# ProProject_FYP_2025-03-13.net
KiCad netlist of a schematic drawn in EasyEDA Pro
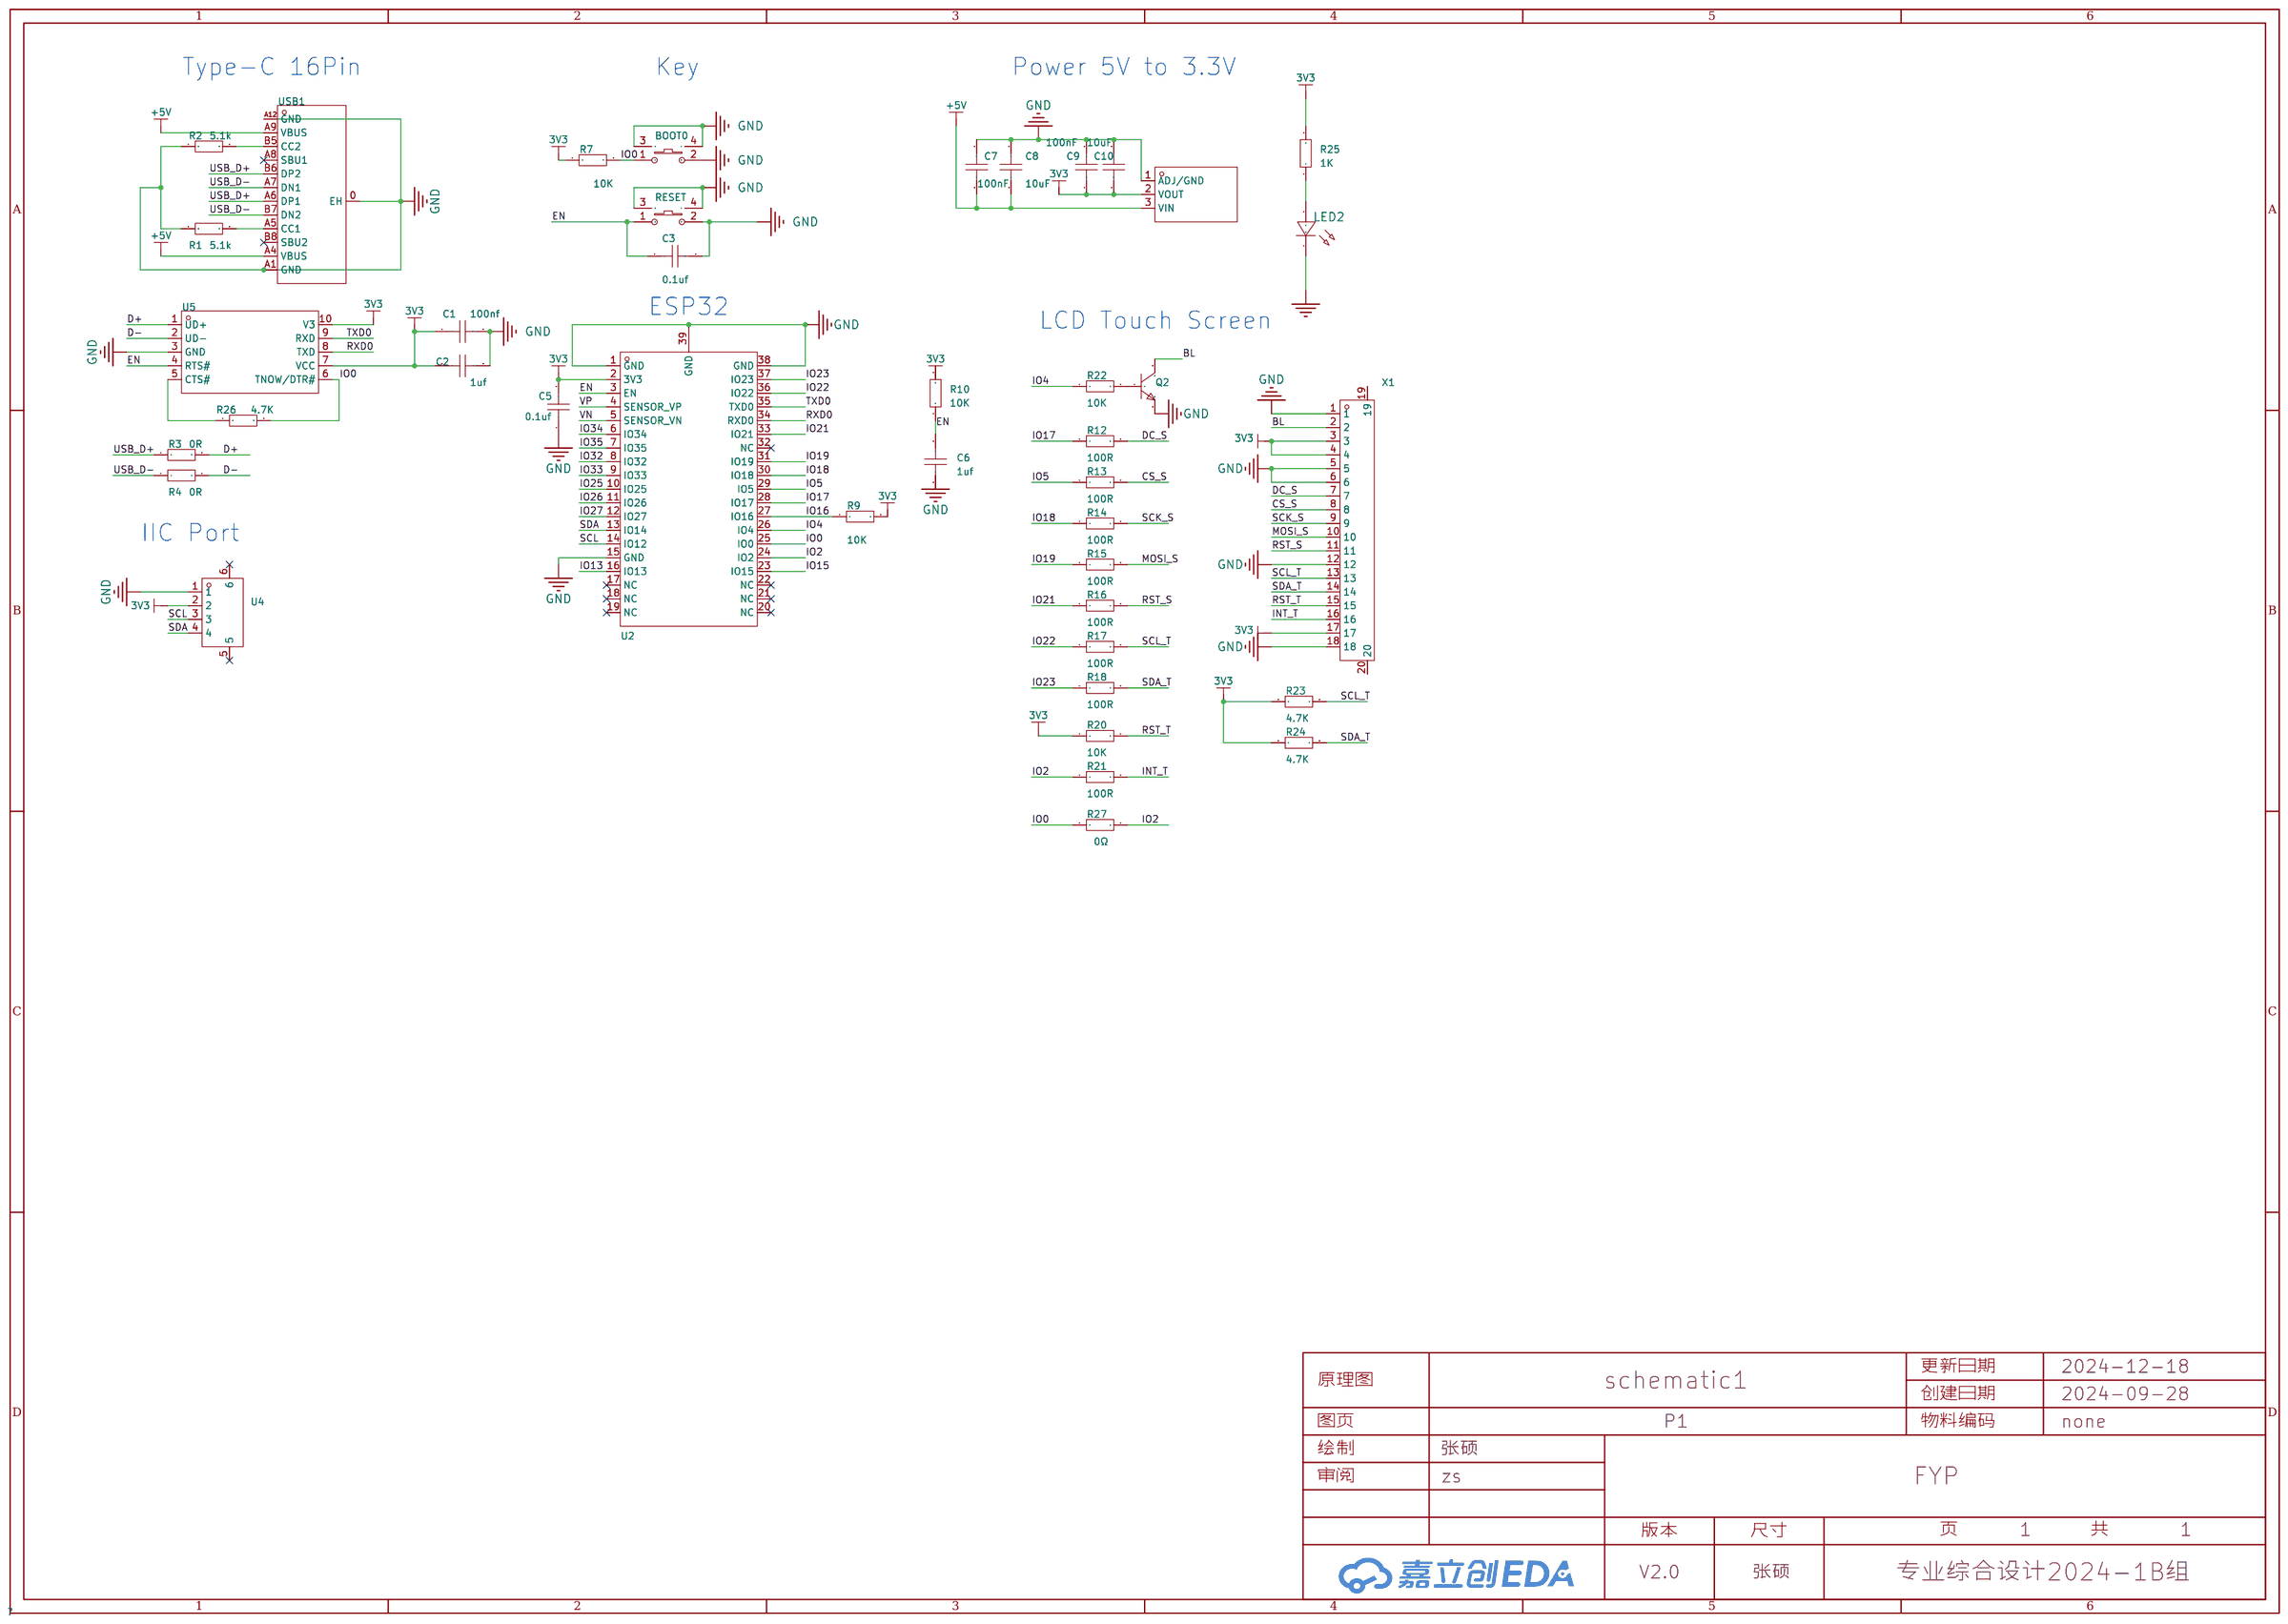
[diagram p0: schematic sheet]

(export (version "E")
  (design (tool "Eeschema 10.0.6"))
  (components
    (comp (ref "BOOT0")
      (value "TS24CA 250gf 013")
      (footprint "easyedapro:SW-SMD_L4.7-W3.5-P3.35-EH")
      (fields (field (name "Manufacturer") "SHOU HAN(首韩)"))
      (libsource (lib "easyedapro") (part "TS24CA 250GF 013"))
    )
    (comp (ref "C1")
      (value "100nf")
      (footprint "easyedapro:C0603")
      (libsource (lib "easyedapro") (part "CapAcitance"))
    )
    (comp (ref "C2")
      (value "1uf")
      (footprint "easyedapro:C0603")
      (libsource (lib "easyedapro") (part "CapAcitance"))
    )
    (comp (ref "C3")
      (value "0.1uf")
      (footprint "easyedapro:C0603")
      (libsource (lib "easyedapro") (part "CapAcitance"))
    )
    (comp (ref "C5")
      (value "0.1uf")
      (footprint "easyedapro:C0603")
      (libsource (lib "easyedapro") (part "CapAcitance"))
    )
    (comp (ref "C6")
      (value "1uf")
      (footprint "easyedapro:C0603")
      (libsource (lib "easyedapro") (part "CapAcitance"))
    )
    (comp (ref "C7")
      (value "100nF")
      (footprint "easyedapro:C0603")
      (libsource (lib "easyedapro") (part "CapAcitance"))
    )
    (comp (ref "C8")
      (value "10uF")
      (footprint "easyedapro:C0603")
      (libsource (lib "easyedapro") (part "CapAcitance"))
    )
    (comp (ref "C9")
      (value "100nF")
      (footprint "easyedapro:C0603")
      (libsource (lib "easyedapro") (part "CapAcitance"))
    )
    (comp (ref "C10")
      (value "10uF")
      (footprint "easyedapro:C0603")
      (libsource (lib "easyedapro") (part "CapAcitance"))
    )
    (comp (ref "LED2")
      (value "~")
      (footprint "easyedapro:LED_0603")
      (libsource (lib "easyedapro") (part "LED_R"))
    )
    (comp (ref "Q2")
      (value "~")
      (footprint "easyedapro:S8050_SOT-23")
      (libsource (lib "easyedapro") (part "NPN"))
    )
    (comp (ref "Q4")
      (value "AMS1117-3.3V")
      (footprint "easyedapro:SOT-89-3_L4.5-W2.5-P1.50-LS4.2-BR")
      (description "输出类型:固定;最大输入电压:18V;输出电压:3.3V;最大输出电流:1A;输出极性:正极;")
      (fields (field (name "Manufacturer") "MSKSEMI(美森科)"))
      (libsource (lib "easyedapro") (part "AMS1117-3.3V_C5120796"))
    )
    (comp (ref "R1") (value "5.1k") (footprint "easyedapro:R0402") (libsource (lib "easyedapro") (part "电阻")))
    (comp (ref "R2") (value "5.1k") (footprint "easyedapro:R0402") (libsource (lib "easyedapro") (part "电阻")))
    (comp (ref "R3") (value "0R") (footprint "easyedapro:R0402") (libsource (lib "easyedapro") (part "电阻")))
    (comp (ref "R4") (value "0R") (footprint "easyedapro:R0402") (libsource (lib "easyedapro") (part "电阻")))
    (comp (ref "R7") (value "10K") (footprint "easyedapro:R0402") (libsource (lib "easyedapro") (part "电阻")))
    (comp (ref "R9") (value "10K") (footprint "easyedapro:R0402") (libsource (lib "easyedapro") (part "电阻")))
    (comp (ref "R10") (value "10K") (footprint "easyedapro:R0402") (libsource (lib "easyedapro") (part "电阻")))
    (comp (ref "R12")
      (value "100R")
      (footprint "easyedapro:R0402")
      (libsource (lib "easyedapro") (part "电阻"))
    )
    (comp (ref "R13")
      (value "100R")
      (footprint "easyedapro:R0402")
      (libsource (lib "easyedapro") (part "电阻"))
    )
    (comp (ref "R14")
      (value "100R")
      (footprint "easyedapro:R0402")
      (libsource (lib "easyedapro") (part "电阻"))
    )
    (comp (ref "R15")
      (value "100R")
      (footprint "easyedapro:R0402")
      (libsource (lib "easyedapro") (part "电阻"))
    )
    (comp (ref "R16")
      (value "100R")
      (footprint "easyedapro:R0402")
      (libsource (lib "easyedapro") (part "电阻"))
    )
    (comp (ref "R17")
      (value "100R")
      (footprint "easyedapro:R0402")
      (libsource (lib "easyedapro") (part "电阻"))
    )
    (comp (ref "R18")
      (value "100R")
      (footprint "easyedapro:R0402")
      (libsource (lib "easyedapro") (part "电阻"))
    )
    (comp (ref "R20") (value "10K") (footprint "easyedapro:R0402") (libsource (lib "easyedapro") (part "电阻")))
    (comp (ref "R21")
      (value "100R")
      (footprint "easyedapro:R0402")
      (libsource (lib "easyedapro") (part "电阻"))
    )
    (comp (ref "R22") (value "10K") (footprint "easyedapro:R0402") (libsource (lib "easyedapro") (part "电阻")))
    (comp (ref "R23")
      (value "4.7K")
      (footprint "easyedapro:R0402")
      (libsource (lib "easyedapro") (part "电阻"))
    )
    (comp (ref "R24")
      (value "4.7K")
      (footprint "easyedapro:R0402")
      (libsource (lib "easyedapro") (part "电阻"))
    )
    (comp (ref "R25") (value "1K") (footprint "easyedapro:R0402") (libsource (lib "easyedapro") (part "电阻")))
    (comp (ref "R26")
      (value "4.7K")
      (footprint "easyedapro:R0402")
      (libsource (lib "easyedapro") (part "电阻"))
    )
    (comp (ref "R27") (value "0Ω") (footprint "easyedapro:R0402") (libsource (lib "easyedapro") (part "电阻")))
    (comp (ref "RESET")
      (value "TS24CA 250gf 013")
      (footprint "easyedapro:SW-SMD_L4.7-W3.5-P3.35-EH")
      (fields (field (name "Manufacturer") "SHOU HAN(首韩)"))
      (libsource (lib "easyedapro") (part "TS24CA 250GF 013"))
    )
    (comp (ref "U2")
      (value "ESP32-WROOM-32E-N4")
      (footprint "easyedapro:WIFI-SMD_ESP32-WROOM-32E")
      (description "ESP32-WROOM-32E 集成 ESP32-D0WD-V3 芯片，具有高的稳定性和安全性能。")
      (fields (field (name "Manufacturer") "ESPRESSIF(乐鑫)"))
      (libsource (lib "easyedapro") (part "ESP32-WROOM-32E(4MB)"))
    )
    (comp (ref "U4")
      (value "WAFER-GH1.25-4PWB")
      (footprint "easyedapro:CONN-SMD_4P-P1.25_XUNPU_WAFER-GH1.25-4PWB")
      (description "插针结构:1x4P;间距:1.25mm;安装方式:卧贴;参考系列:GH;总PIN数:4P;排数:1;每排PIN数:4;额定电流:1A;工作温度范围:-25°C~+85°C;")
      (fields (field (name "Manufacturer") "XUNPU(讯普)"))
      (libsource (lib "easyedapro") (part "WAFER-GH1.25-4PWB"))
    )
    (comp (ref "U5")
      (value "CH340X")
      (footprint "easyedapro:MSOP-10_L3.0-W3.0-P0.50-LS5.0-BL")
      (fields (field (name "Manufacturer") "WCH(南京沁恒)"))
      (libsource (lib "easyedapro") (part "CH340X"))
    )
    (comp (ref "USB1")
      (value "TYPE-C 16P QTWT")
      (footprint "easyedapro:USB-TYPE-C-SMD_TYPE-C-16P-QTWT")
      (fields (field (name "Manufacturer") "SHOU HAN(首韩)"))
      (libsource (lib "easyedapro") (part "TYPE-C 16P QTWT"))
    )
    (comp (ref "X1")
      (value "AFC07-S18FCA-00")
      (footprint "easyedapro:FPC-SMD_AFC07-S18FCA-00")
      (description "锁定特性:抽屉式;触点类型:下接;触点数量:18P;间距:0.5mm;安装类型:卧贴;工作温度范围:-;")
      (fields (field (name "Manufacturer") "JS(钜硕电子)"))
      (libsource (lib "easyedapro") (part "AFC07-S18FCA-00"))
    )
  )
  (nets
    (net (code "1") (name "+5V") (class "Default")
      (node (ref "C7") (pin "1") (pinfunction "1_1") (pintype "input"))
      (node (ref "C8") (pin "1") (pinfunction "1_1") (pintype "input"))
      (node (ref "Q4") (pin "3") (pinfunction "VIN_3") (pintype "unspecified"))
      (node (ref "USB1") (pin "A4") (pinfunction "VBUS_A4") (pintype "unspecified"))
      (node (ref "USB1") (pin "A9") (pinfunction "VBUS_A9") (pintype "unspecified"))
    )
    (net (code "2") (name "/BL") (class "Default")
      (node (ref "Q2") (pin "3") (pinfunction "3_3") (pintype "unspecified"))
      (node (ref "X1") (pin "2") (pinfunction "2_2") (pintype "unspecified"))
    )
    (net (code "3") (name "/CS_S") (class "Default")
      (node (ref "R13") (pin "2") (pinfunction "2_2") (pintype "input"))
      (node (ref "X1") (pin "8") (pinfunction "8_8") (pintype "unspecified"))
    )
    (net (code "4") (name "/D+") (class "Default")
      (node (ref "R3") (pin "2") (pinfunction "2_2") (pintype "input"))
      (node (ref "U5") (pin "1") (pinfunction "UD+_1") (pintype "unspecified"))
    )
    (net (code "5") (name "/D-") (class "Default")
      (node (ref "R4") (pin "2") (pinfunction "2_2") (pintype "input"))
      (node (ref "U5") (pin "2") (pinfunction "UD-_2") (pintype "unspecified"))
    )
    (net (code "6") (name "/DC_S") (class "Default")
      (node (ref "R12") (pin "2") (pinfunction "2_2") (pintype "input"))
      (node (ref "X1") (pin "7") (pinfunction "7_7") (pintype "unspecified"))
    )
    (net (code "7") (name "/EN") (class "Default")
      (node (ref "C3") (pin "1") (pinfunction "1_1") (pintype "input"))
      (node (ref "C6") (pin "1") (pinfunction "1_1") (pintype "input"))
      (node (ref "R10") (pin "1") (pinfunction "1_1") (pintype "input"))
      (node (ref "RESET") (pin "1") (pinfunction "1_1") (pintype "unspecified"))
      (node (ref "U2") (pin "3") (pinfunction "EN_3") (pintype "unspecified"))
      (node (ref "U5") (pin "4") (pinfunction "RTS#_4") (pintype "unspecified"))
    )
    (net (code "8") (name "/INT_T") (class "Default")
      (node (ref "R21") (pin "2") (pinfunction "2_2") (pintype "input"))
      (node (ref "X1") (pin "16") (pinfunction "16_16") (pintype "unspecified"))
    )
    (net (code "9") (name "/IO0") (class "Default")
      (node (ref "BOOT0") (pin "1") (pinfunction "1_1") (pintype "unspecified"))
      (node (ref "R26") (pin "2") (pinfunction "2_2") (pintype "input"))
      (node (ref "R27") (pin "1") (pinfunction "1_1") (pintype "input"))
      (node (ref "R7") (pin "2") (pinfunction "2_2") (pintype "input"))
      (node (ref "U2") (pin "25") (pinfunction "IO0_25") (pintype "unspecified"))
      (node (ref "U5") (pin "6") (pinfunction "TNOW/DTR#_6") (pintype "unspecified"))
    )
    (net (code "10") (name "/IO2") (class "Default")
      (node (ref "R21") (pin "1") (pinfunction "1_1") (pintype "input"))
      (node (ref "R27") (pin "2") (pinfunction "2_2") (pintype "input"))
      (node (ref "U2") (pin "24") (pinfunction "IO2_24") (pintype "unspecified"))
    )
    (net (code "11") (name "/IO4") (class "Default")
      (node (ref "R22") (pin "1") (pinfunction "1_1") (pintype "input"))
      (node (ref "U2") (pin "26") (pinfunction "IO4_26") (pintype "unspecified"))
    )
    (net (code "12") (name "/IO5") (class "Default")
      (node (ref "R13") (pin "1") (pinfunction "1_1") (pintype "input"))
      (node (ref "U2") (pin "29") (pinfunction "IO5_29") (pintype "unspecified"))
    )
    (net (code "13") (name "/IO13") (class "Default")
      (node (ref "U2") (pin "16") (pinfunction "IO13_16") (pintype "unspecified"))
    )
    (net (code "14") (name "/IO15") (class "Default")
      (node (ref "U2") (pin "23") (pinfunction "IO15_23") (pintype "unspecified"))
    )
    (net (code "15") (name "/IO16") (class "Default")
      (node (ref "R9") (pin "1") (pinfunction "1_1") (pintype "input"))
      (node (ref "U2") (pin "27") (pinfunction "IO16_27") (pintype "unspecified"))
    )
    (net (code "16") (name "/IO17") (class "Default")
      (node (ref "R12") (pin "1") (pinfunction "1_1") (pintype "input"))
      (node (ref "U2") (pin "28") (pinfunction "IO17_28") (pintype "unspecified"))
    )
    (net (code "17") (name "/IO18") (class "Default")
      (node (ref "R14") (pin "1") (pinfunction "1_1") (pintype "input"))
      (node (ref "U2") (pin "30") (pinfunction "IO18_30") (pintype "unspecified"))
    )
    (net (code "18") (name "/IO19") (class "Default")
      (node (ref "R15") (pin "1") (pinfunction "1_1") (pintype "input"))
      (node (ref "U2") (pin "31") (pinfunction "IO19_31") (pintype "unspecified"))
    )
    (net (code "19") (name "/IO21") (class "Default")
      (node (ref "R16") (pin "1") (pinfunction "1_1") (pintype "input"))
      (node (ref "U2") (pin "33") (pinfunction "IO21_33") (pintype "unspecified"))
    )
    (net (code "20") (name "/IO22") (class "Default")
      (node (ref "R17") (pin "1") (pinfunction "1_1") (pintype "input"))
      (node (ref "U2") (pin "36") (pinfunction "IO22_36") (pintype "unspecified"))
    )
    (net (code "21") (name "/IO23") (class "Default")
      (node (ref "R18") (pin "1") (pinfunction "1_1") (pintype "input"))
      (node (ref "U2") (pin "37") (pinfunction "IO23_37") (pintype "unspecified"))
    )
    (net (code "22") (name "/IO25") (class "Default")
      (node (ref "U2") (pin "10") (pinfunction "IO25_10") (pintype "unspecified"))
    )
    (net (code "23") (name "/IO26") (class "Default")
      (node (ref "U2") (pin "11") (pinfunction "IO26_11") (pintype "unspecified"))
    )
    (net (code "24") (name "/IO27") (class "Default")
      (node (ref "U2") (pin "12") (pinfunction "IO27_12") (pintype "unspecified"))
    )
    (net (code "25") (name "/IO32") (class "Default")
      (node (ref "U2") (pin "8") (pinfunction "IO32_8") (pintype "unspecified"))
    )
    (net (code "26") (name "/IO33") (class "Default")
      (node (ref "U2") (pin "9") (pinfunction "IO33_9") (pintype "unspecified"))
    )
    (net (code "27") (name "/IO34") (class "Default")
      (node (ref "U2") (pin "6") (pinfunction "IO34_6") (pintype "unspecified"))
    )
    (net (code "28") (name "/IO35") (class "Default")
      (node (ref "U2") (pin "7") (pinfunction "IO35_7") (pintype "unspecified"))
    )
    (net (code "29") (name "/MOSI_S") (class "Default")
      (node (ref "R15") (pin "2") (pinfunction "2_2") (pintype "input"))
      (node (ref "X1") (pin "10") (pinfunction "10_10") (pintype "unspecified"))
    )
    (net (code "30") (name "/RST_S") (class "Default")
      (node (ref "R16") (pin "2") (pinfunction "2_2") (pintype "input"))
      (node (ref "X1") (pin "11") (pinfunction "11_11") (pintype "unspecified"))
    )
    (net (code "31") (name "/RST_T") (class "Default")
      (node (ref "R20") (pin "2") (pinfunction "2_2") (pintype "input"))
      (node (ref "X1") (pin "15") (pinfunction "15_15") (pintype "unspecified"))
    )
    (net (code "32") (name "/RXD0") (class "Default")
      (node (ref "U2") (pin "34") (pinfunction "RXD0_34") (pintype "unspecified"))
      (node (ref "U5") (pin "8") (pinfunction "TXD_8") (pintype "unspecified"))
    )
    (net (code "33") (name "/SCK_S") (class "Default")
      (node (ref "R14") (pin "2") (pinfunction "2_2") (pintype "input"))
      (node (ref "X1") (pin "9") (pinfunction "9_9") (pintype "unspecified"))
    )
    (net (code "34") (name "/SCL") (class "Default")
      (node (ref "U2") (pin "14") (pinfunction "IO12_14") (pintype "unspecified"))
      (node (ref "U4") (pin "3") (pinfunction "3_3") (pintype "unspecified"))
    )
    (net (code "35") (name "/SCL_T") (class "Default")
      (node (ref "R17") (pin "2") (pinfunction "2_2") (pintype "input"))
      (node (ref "R23") (pin "2") (pinfunction "2_2") (pintype "input"))
      (node (ref "X1") (pin "13") (pinfunction "13_13") (pintype "unspecified"))
    )
    (net (code "36") (name "/SDA") (class "Default")
      (node (ref "U2") (pin "13") (pinfunction "IO14_13") (pintype "unspecified"))
      (node (ref "U4") (pin "4") (pinfunction "4_4") (pintype "unspecified"))
    )
    (net (code "37") (name "/SDA_T") (class "Default")
      (node (ref "R18") (pin "2") (pinfunction "2_2") (pintype "input"))
      (node (ref "R24") (pin "2") (pinfunction "2_2") (pintype "input"))
      (node (ref "X1") (pin "14") (pinfunction "14_14") (pintype "unspecified"))
    )
    (net (code "38") (name "/TXD0") (class "Default")
      (node (ref "U2") (pin "35") (pinfunction "TXD0_35") (pintype "unspecified"))
      (node (ref "U5") (pin "9") (pinfunction "RXD_9") (pintype "unspecified"))
    )
    (net (code "39") (name "/USB_D+") (class "Default")
      (node (ref "R3") (pin "1") (pinfunction "1_1") (pintype "input"))
      (node (ref "USB1") (pin "A6") (pinfunction "DP1_A6") (pintype "unspecified"))
      (node (ref "USB1") (pin "B6") (pinfunction "DP2_B6") (pintype "unspecified"))
    )
    (net (code "40") (name "/USB_D-") (class "Default")
      (node (ref "R4") (pin "1") (pinfunction "1_1") (pintype "input"))
      (node (ref "USB1") (pin "A7") (pinfunction "DN1_A7") (pintype "unspecified"))
      (node (ref "USB1") (pin "B7") (pinfunction "DN2_B7") (pintype "unspecified"))
    )
    (net (code "41") (name "/VN") (class "Default")
      (node (ref "U2") (pin "5") (pinfunction "SENSOR_VN_5") (pintype "unspecified"))
    )
    (net (code "42") (name "/VP") (class "Default")
      (node (ref "U2") (pin "4") (pinfunction "SENSOR_VP_4") (pintype "unspecified"))
    )
    (net (code "43") (name "3V3") (class "Default")
      (node (ref "C1") (pin "1") (pinfunction "1_1") (pintype "input"))
      (node (ref "C10") (pin "1") (pinfunction "1_1") (pintype "input"))
      (node (ref "C2") (pin "1") (pinfunction "1_1") (pintype "input"))
      (node (ref "C5") (pin "2") (pinfunction "2_2") (pintype "input"))
      (node (ref "C9") (pin "1") (pinfunction "1_1") (pintype "input"))
      (node (ref "Q4") (pin "2") (pinfunction "VOUT_2") (pintype "unspecified"))
      (node (ref "R10") (pin "2") (pinfunction "2_2") (pintype "input"))
      (node (ref "R20") (pin "1") (pinfunction "1_1") (pintype "input"))
      (node (ref "R23") (pin "1") (pinfunction "1_1") (pintype "input"))
      (node (ref "R24") (pin "1") (pinfunction "1_1") (pintype "input"))
      (node (ref "R25") (pin "2") (pinfunction "2_2") (pintype "input"))
      (node (ref "R7") (pin "1") (pinfunction "1_1") (pintype "input"))
      (node (ref "R9") (pin "2") (pinfunction "2_2") (pintype "input"))
      (node (ref "U2") (pin "2") (pinfunction "3V3_2") (pintype "unspecified"))
      (node (ref "U4") (pin "2") (pinfunction "2_2") (pintype "unspecified"))
      (node (ref "U5") (pin "10") (pinfunction "V3_10") (pintype "unspecified"))
      (node (ref "U5") (pin "7") (pinfunction "VCC_7") (pintype "unspecified"))
      (node (ref "X1") (pin "17") (pinfunction "17_17") (pintype "unspecified"))
      (node (ref "X1") (pin "3") (pinfunction "3_3") (pintype "unspecified"))
      (node (ref "X1") (pin "4") (pinfunction "4_4") (pintype "unspecified"))
    )
    (net (code "44") (name "GND") (class "Default")
      (node (ref "BOOT0") (pin "2") (pinfunction "2_2") (pintype "unspecified"))
      (node (ref "BOOT0") (pin "3") (pinfunction "3_3") (pintype "unspecified"))
      (node (ref "BOOT0") (pin "4") (pinfunction "4_4") (pintype "unspecified"))
      (node (ref "C1") (pin "2") (pinfunction "2_2") (pintype "input"))
      (node (ref "C10") (pin "2") (pinfunction "2_2") (pintype "input"))
      (node (ref "C2") (pin "2") (pinfunction "2_2") (pintype "input"))
      (node (ref "C3") (pin "2") (pinfunction "2_2") (pintype "input"))
      (node (ref "C5") (pin "1") (pinfunction "1_1") (pintype "input"))
      (node (ref "C6") (pin "2") (pinfunction "2_2") (pintype "input"))
      (node (ref "C7") (pin "2") (pinfunction "2_2") (pintype "input"))
      (node (ref "C8") (pin "2") (pinfunction "2_2") (pintype "input"))
      (node (ref "C9") (pin "2") (pinfunction "2_2") (pintype "input"))
      (node (ref "LED2") (pin "1") (pinfunction "C_1") (pintype "input"))
      (node (ref "Q2") (pin "2") (pinfunction "2_2") (pintype "unspecified"))
      (node (ref "Q4") (pin "1") (pinfunction "ADJ/GND_1") (pintype "unspecified"))
      (node (ref "R1") (pin "1") (pinfunction "1_1") (pintype "input"))
      (node (ref "R2") (pin "1") (pinfunction "1_1") (pintype "input"))
      (node (ref "RESET") (pin "2") (pinfunction "2_2") (pintype "unspecified"))
      (node (ref "RESET") (pin "3") (pinfunction "3_3") (pintype "unspecified"))
      (node (ref "RESET") (pin "4") (pinfunction "4_4") (pintype "unspecified"))
      (node (ref "U2") (pin "1") (pinfunction "GND_1") (pintype "unspecified"))
      (node (ref "U2") (pin "15") (pinfunction "GND_15") (pintype "unspecified"))
      (node (ref "U2") (pin "38") (pinfunction "GND_38") (pintype "unspecified"))
      (node (ref "U2") (pin "39") (pinfunction "GND_39") (pintype "unspecified"))
      (node (ref "U4") (pin "1") (pinfunction "1_1") (pintype "unspecified"))
      (node (ref "U5") (pin "3") (pinfunction "GND_3") (pintype "unspecified"))
      (node (ref "USB1") (pin "0") (pinfunction "EH_0") (pintype "unspecified"))
      (node (ref "USB1") (pin "A1") (pinfunction "GND_A1") (pintype "unspecified"))
      (node (ref "USB1") (pin "A12") (pinfunction "GND_A12") (pintype "unspecified"))
      (node (ref "X1") (pin "1") (pinfunction "1_1") (pintype "unspecified"))
      (node (ref "X1") (pin "12") (pinfunction "12_12") (pintype "unspecified"))
      (node (ref "X1") (pin "18") (pinfunction "18_18") (pintype "unspecified"))
      (node (ref "X1") (pin "5") (pinfunction "5_5") (pintype "unspecified"))
      (node (ref "X1") (pin "6") (pinfunction "6_6") (pintype "unspecified"))
    )
    (net (code "45") (name "Net-(LED2-A)") (class "Default")
      (node (ref "LED2") (pin "2") (pinfunction "A_2") (pintype "input"))
      (node (ref "R25") (pin "1") (pinfunction "1_1") (pintype "input"))
    )
    (net (code "46") (name "Net-(Q2-Pad1)") (class "Default")
      (node (ref "Q2") (pin "1") (pinfunction "1_1") (pintype "unspecified"))
      (node (ref "R22") (pin "2") (pinfunction "2_2") (pintype "input"))
    )
    (net (code "47") (name "Net-(U5-CTS#)") (class "Default")
      (node (ref "R26") (pin "1") (pinfunction "1_1") (pintype "input"))
      (node (ref "U5") (pin "5") (pinfunction "CTS#_5") (pintype "unspecified"))
    )
    (net (code "48") (name "Net-(USB1-CC1)") (class "Default")
      (node (ref "R1") (pin "2") (pinfunction "2_2") (pintype "input"))
      (node (ref "USB1") (pin "A5") (pinfunction "CC1_A5") (pintype "unspecified"))
    )
    (net (code "49") (name "Net-(USB1-CC2)") (class "Default")
      (node (ref "R2") (pin "2") (pinfunction "2_2") (pintype "input"))
      (node (ref "USB1") (pin "B5") (pinfunction "CC2_B5") (pintype "unspecified"))
    )
    (net (code "50") (name "unconnected-(U2-NC-Pad17)") (class "Default")
      (node (ref "U2") (pin "17") (pinfunction "NC_17") (pintype "unspecified+no_connect"))
    )
    (net (code "51") (name "unconnected-(U2-NC-Pad18)") (class "Default")
      (node (ref "U2") (pin "18") (pinfunction "NC_18") (pintype "unspecified+no_connect"))
    )
    (net (code "52") (name "unconnected-(U2-NC-Pad19)") (class "Default")
      (node (ref "U2") (pin "19") (pinfunction "NC_19") (pintype "unspecified+no_connect"))
    )
    (net (code "53") (name "unconnected-(U2-NC-Pad20)") (class "Default")
      (node (ref "U2") (pin "20") (pinfunction "NC_20") (pintype "unspecified+no_connect"))
    )
    (net (code "54") (name "unconnected-(U2-NC-Pad21)") (class "Default")
      (node (ref "U2") (pin "21") (pinfunction "NC_21") (pintype "unspecified+no_connect"))
    )
    (net (code "55") (name "unconnected-(U2-NC-Pad22)") (class "Default")
      (node (ref "U2") (pin "22") (pinfunction "NC_22") (pintype "unspecified+no_connect"))
    )
    (net (code "56") (name "unconnected-(U2-NC-Pad32)") (class "Default")
      (node (ref "U2") (pin "32") (pinfunction "NC_32") (pintype "unspecified+no_connect"))
    )
    (net (code "57") (name "unconnected-(U4-Pad5)") (class "Default")
      (node (ref "U4") (pin "5") (pinfunction "5_5") (pintype "unspecified+no_connect"))
    )
    (net (code "58") (name "unconnected-(U4-Pad6)") (class "Default")
      (node (ref "U4") (pin "6") (pinfunction "6_6") (pintype "unspecified+no_connect"))
    )
    (net (code "59") (name "unconnected-(USB1-SBU1-PadA8)") (class "Default")
      (node (ref "USB1") (pin "A8") (pinfunction "SBU1_A8") (pintype "unspecified+no_connect"))
    )
    (net (code "60") (name "unconnected-(USB1-SBU2-PadB8)") (class "Default")
      (node (ref "USB1") (pin "B8") (pinfunction "SBU2_B8") (pintype "unspecified+no_connect"))
    )
    (net (code "61") (name "unconnected-(X1-Pad19)") (class "Default")
      (node (ref "X1") (pin "19") (pinfunction "19_19") (pintype "unspecified"))
    )
    (net (code "62") (name "unconnected-(X1-Pad20)") (class "Default")
      (node (ref "X1") (pin "20") (pinfunction "20_20") (pintype "unspecified"))
    )
  )
)
